# wireless-dong-mk-2_3.net
KiCad netlist of a schematic drawn in EAGLE
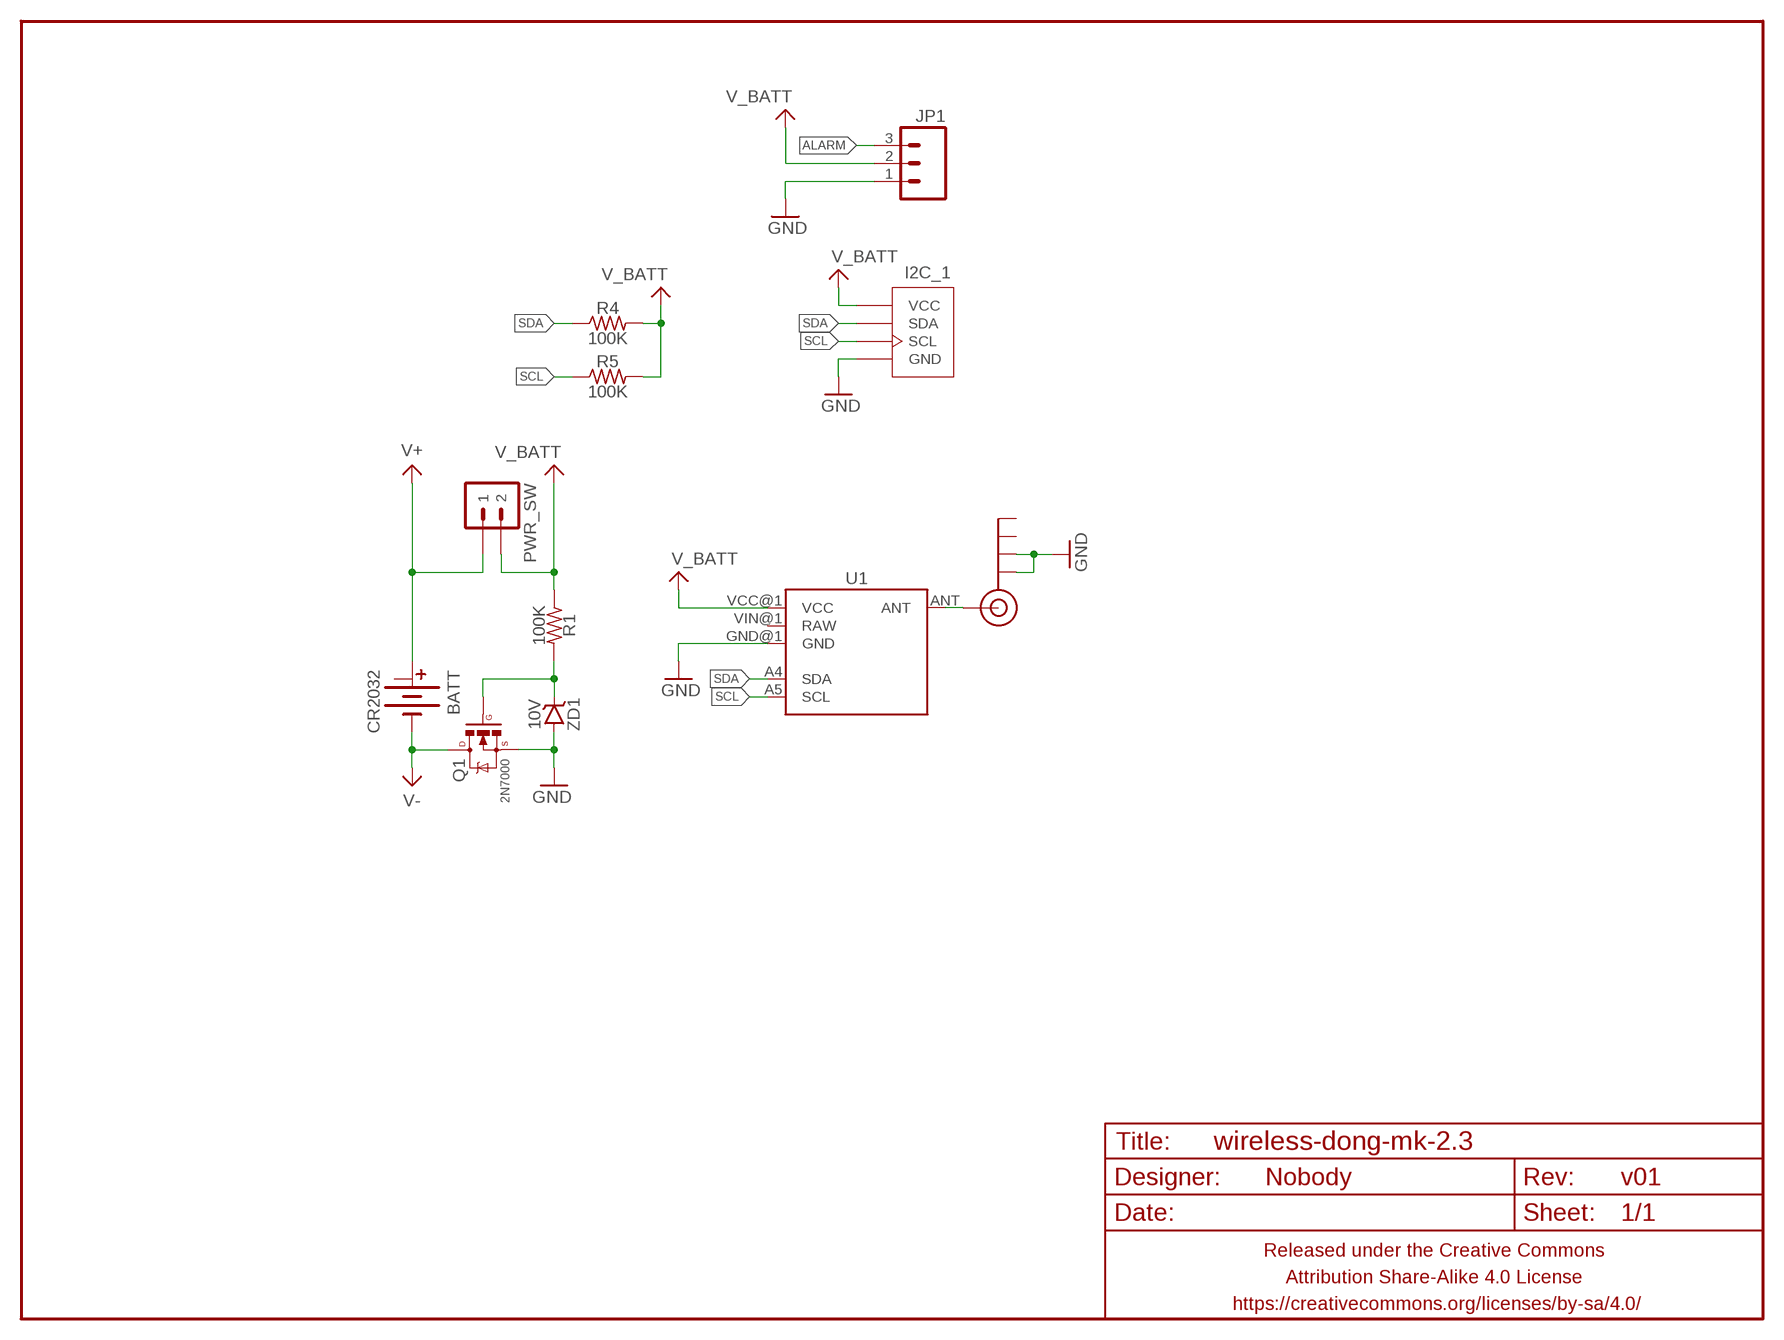
[diagram p0: schematic, sheet 1]

(export (version "E")
  (design (tool "Eeschema 10.0.6"))
  (components
    (comp (ref "ANT")
      (value "SMA_EDGE")
      (footprint "eagle-import:SMA-EDGE")
      (libsource (lib "eagle-import") (part "SMA_EDGE"))
    )
    (comp (ref "BATT")
      (value "CR2032")
      (footprint "eagle-import:BATTCON_20MM_MINE_STAHPIT")
      (libsource (lib "eagle-import") (part "BATTERY-COINCR2032_SMD_TIGHT"))
    )
    (comp (ref "FRAME1")
      (value "FRAME-LETTERNO_PACKAGE")
      (footprint "eagle-import:DUMMY")
      (fields (field (name "DESIGNER") "Nobody"))
      (libsource (lib "eagle-import") (part "FRAME-LETTERNO_PACKAGE"))
    )
    (comp (ref "I2C_1")
      (value "M04-I2CJST-4-PH-RA-CENTERED")
      (footprint "eagle-import:1X04-JST-PH-RA-PTH-I2C-CENTERED")
      (libsource (lib "eagle-import") (part "M04-I2CJST-4-PH-RA-CENTERED"))
    )
    (comp (ref "JP1")
      (value "M03JST-PTH")
      (footprint "eagle-import:JST-3-PH-RA-PTH")
      (libsource (lib "eagle-import") (part "M03JST-PTH"))
    )
    (comp (ref "PWR_SW")
      (value "M02PTH-CENTERED")
      (footprint "eagle-import:1X02-CENTER")
      (libsource (lib "eagle-import") (part "M02PTH-CENTERED"))
    )
    (comp (ref "Q1")
      (value "2N7000")
      (footprint "eagle-import:SOT23")
      (libsource (lib "eagle-import") (part "MOSFET-NCHANNELIRLML2502"))
    )
    (comp (ref "R1")
      (value "100K")
      (footprint "eagle-import:R0805")
      (libsource (lib "eagle-import") (part "RESISTORR0805"))
    )
    (comp (ref "R4")
      (value "100K")
      (footprint "eagle-import:R0805")
      (libsource (lib "eagle-import") (part "RESISTORR0805"))
    )
    (comp (ref "R5")
      (value "100K")
      (footprint "eagle-import:R0805")
      (libsource (lib "eagle-import") (part "RESISTORR0805"))
    )
    (comp (ref "U1")
      (value "MOTEINO_BOAT")
      (footprint "eagle-import:MOTEINO_BOAT")
      (libsource (lib "eagle-import") (part "MOTEINO_BOAT"))
    )
    (comp (ref "ZD1")
      (value "10V")
      (footprint "eagle-import:SOT23")
      (libsource (lib "eagle-import") (part "DIODE-ZENERSOT23"))
    )
  )
  (nets
    (net (code "1") (name "ALARM") (class "Default")
      (node (ref "JP1") (pin "3") (pinfunction "3_3") (pintype "passive"))
    )
    (net (code "2") (name "GND") (class "Default")
      (node (ref "ANT") (pin "GND@0") (pinfunction "GND_GND@0") (pintype "bidirectional"))
      (node (ref "ANT") (pin "GND@1") (pinfunction "GND_GND@1") (pintype "bidirectional"))
      (node (ref "I2C_1") (pin "1") (pinfunction "GND_1") (pintype "bidirectional"))
      (node (ref "JP1") (pin "1") (pinfunction "1_1") (pintype "passive"))
      (node (ref "Q1") (pin "2") (pinfunction "S_2") (pintype "passive"))
      (node (ref "U1") (pin "GND@1") (pinfunction "GND_GND@1") (pintype "bidirectional"))
      (node (ref "ZD1") (pin "1") (pinfunction "A_1") (pintype "passive"))
      (node (ref "ZD1") (pin "2") (pinfunction "A_2") (pintype "passive"))
    )
    (net (code "3") (name "Net-(ANT-SIGNAL)") (class "Default")
      (node (ref "ANT") (pin "SIG") (pinfunction "SIGNAL_SIG") (pintype "bidirectional"))
      (node (ref "U1") (pin "ANT") (pinfunction "ANT_ANT") (pintype "bidirectional"))
    )
    (net (code "4") (name "Net-(Q1-G)") (class "Default")
      (node (ref "Q1") (pin "1") (pinfunction "G_1") (pintype "passive"))
      (node (ref "R1") (pin "2") (pinfunction "2_2") (pintype "passive"))
      (node (ref "ZD1") (pin "3") (pinfunction "C_3") (pintype "passive"))
    )
    (net (code "5") (name "SCL") (class "Default")
      (node (ref "I2C_1") (pin "4") (pinfunction "SCL_4") (pintype "bidirectional"))
      (node (ref "R5") (pin "1") (pinfunction "1_1") (pintype "passive"))
      (node (ref "U1") (pin "A5") (pinfunction "SCL_A5") (pintype "bidirectional"))
    )
    (net (code "6") (name "SDA") (class "Default")
      (node (ref "I2C_1") (pin "3") (pinfunction "SDA_3") (pintype "bidirectional"))
      (node (ref "R4") (pin "1") (pinfunction "1_1") (pintype "passive"))
      (node (ref "U1") (pin "A4") (pinfunction "SDA_A4") (pintype "bidirectional"))
    )
    (net (code "7") (name "V+") (class "Default")
      (node (ref "BATT") (pin "TOP@1") (pinfunction "+_TOP@1") (pintype "bidirectional"))
      (node (ref "PWR_SW") (pin "1") (pinfunction "1_1") (pintype "passive"))
    )
    (net (code "8") (name "V-") (class "Default")
      (node (ref "BATT") (pin "BOTTOM") (pinfunction "-_BOTTOM") (pintype "bidirectional"))
      (node (ref "Q1") (pin "3") (pinfunction "D_3") (pintype "passive"))
    )
    (net (code "9") (name "V_BATT") (class "Default")
      (node (ref "I2C_1") (pin "2") (pinfunction "VCC_2") (pintype "bidirectional"))
      (node (ref "JP1") (pin "2") (pinfunction "2_2") (pintype "passive"))
      (node (ref "PWR_SW") (pin "2") (pinfunction "2_2") (pintype "passive"))
      (node (ref "R1") (pin "1") (pinfunction "1_1") (pintype "passive"))
      (node (ref "R4") (pin "2") (pinfunction "2_2") (pintype "passive"))
      (node (ref "R5") (pin "2") (pinfunction "2_2") (pintype "passive"))
      (node (ref "U1") (pin "VCC@1") (pinfunction "VCC_VCC@1") (pintype "bidirectional"))
    )
    (net (code "10") (name "unconnected-(ANT-GND-PadGND@2)") (class "Default")
      (node (ref "ANT") (pin "GND@2") (pinfunction "GND_GND@2") (pintype "bidirectional"))
    )
    (net (code "11") (name "unconnected-(ANT-GND-PadGND@3)") (class "Default")
      (node (ref "ANT") (pin "GND@3") (pinfunction "GND_GND@3") (pintype "bidirectional"))
    )
    (net (code "12") (name "unconnected-(BATT-+1-PadTOP@2)") (class "Default")
      (node (ref "BATT") (pin "TOP@2") (pinfunction "+1_TOP@2") (pintype "bidirectional"))
    )
    (net (code "13") (name "unconnected-(U1-RAW-PadVIN@1)") (class "Default")
      (node (ref "U1") (pin "VIN@1") (pinfunction "RAW_VIN@1") (pintype "bidirectional"))
    )
  )
)
